# Analog_Interface.net
KiCad netlist of a schematic drawn in Altium Designer
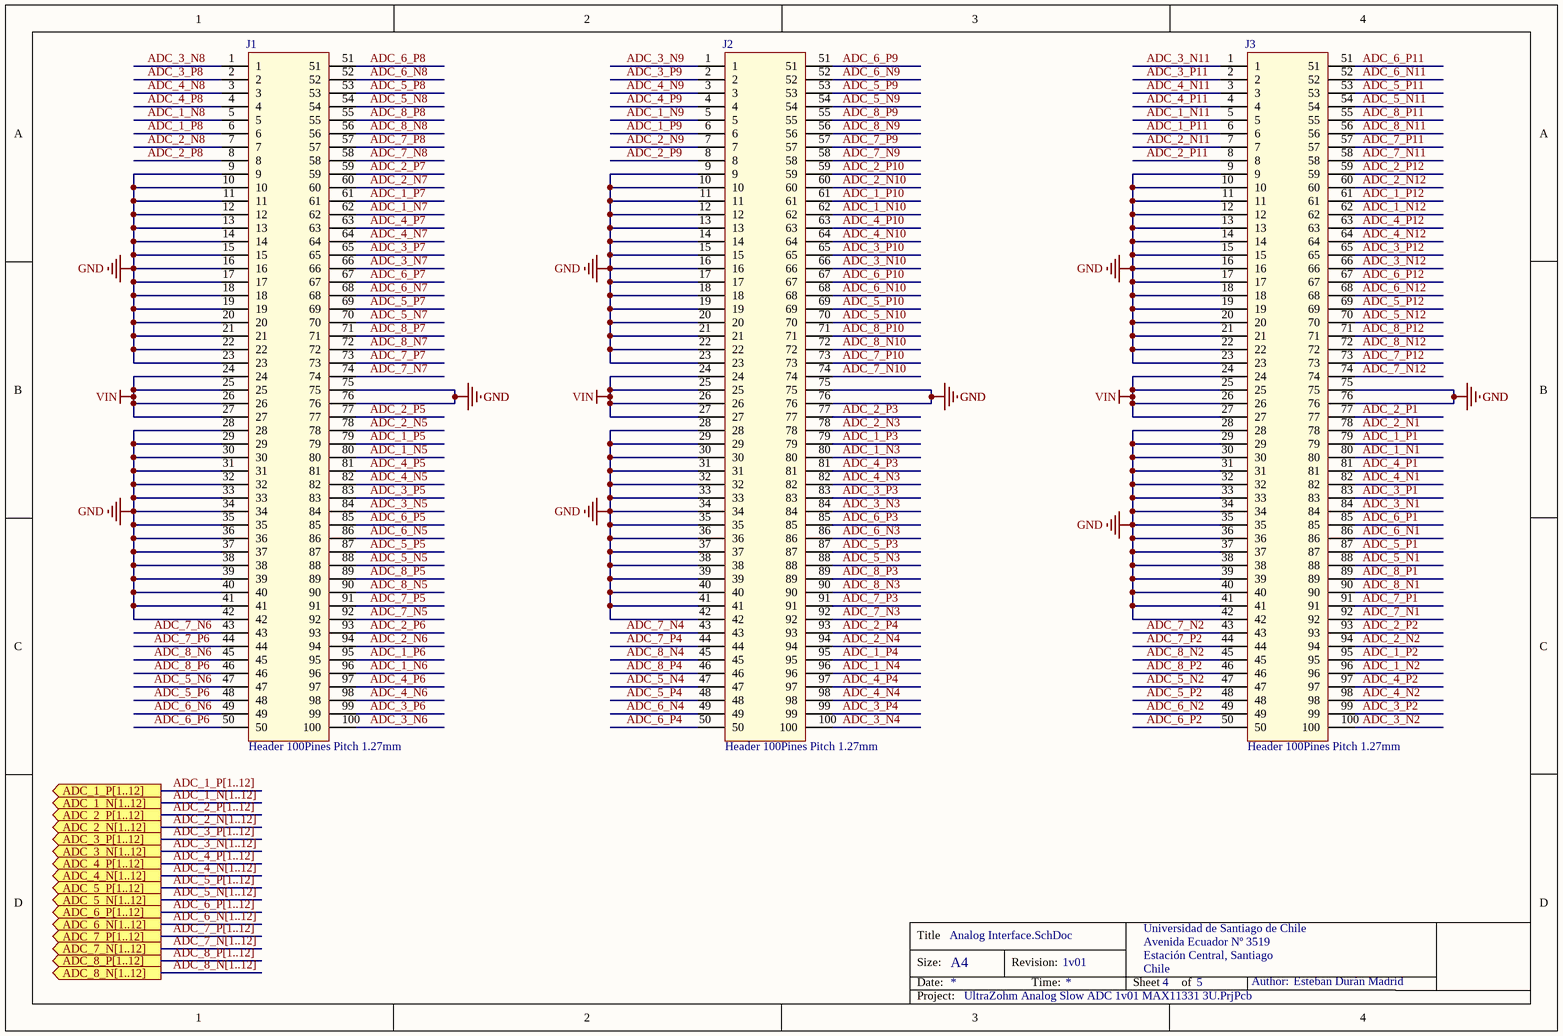
[diagram p0: Analog Interface.SchDoc]

(export (version "E")
  (design (tool "Eeschema 10.0.6"))
  (components
    (comp (ref "J1")
      (value "Header 100Pines Pitch 1.27mm")
      (footprint "Conector TE 100pines (2 filas) Pitch: 1.27mm")
      (description "6-104068-7")
      (libsource (lib "Componentes_SOC") (part "Header 100Pines Pitch 1.27mm"))
    )
    (comp (ref "J2")
      (value "Header 100Pines Pitch 1.27mm")
      (footprint "Conector TE 100pines (2 filas) Pitch: 1.27mm")
      (description "6-104068-7")
      (libsource (lib "Componentes_SOC") (part "Header 100Pines Pitch 1.27mm"))
    )
    (comp (ref "J3")
      (value "Header 100Pines Pitch 1.27mm")
      (footprint "Conector TE 100pines (2 filas) Pitch: 1.27mm")
      (description "6-104068-7")
      (libsource (lib "Componentes_SOC") (part "Header 100Pines Pitch 1.27mm"))
    )
  )
  (nets
    (net (code "1") (name "/ADC_1_N1") (class "Default")
      (node (ref "J3") (pin "80") (pinfunction "80_80") (pintype "passive"))
    )
    (net (code "2") (name "/ADC_1_N2") (class "Default")
      (node (ref "J3") (pin "96") (pinfunction "96_96") (pintype "passive"))
    )
    (net (code "3") (name "/ADC_1_N3") (class "Default")
      (node (ref "J2") (pin "80") (pinfunction "80_80") (pintype "passive"))
    )
    (net (code "4") (name "/ADC_1_N4") (class "Default")
      (node (ref "J2") (pin "96") (pinfunction "96_96") (pintype "passive"))
    )
    (net (code "5") (name "/ADC_1_N5") (class "Default")
      (node (ref "J1") (pin "80") (pinfunction "80_80") (pintype "passive"))
    )
    (net (code "6") (name "/ADC_1_N6") (class "Default")
      (node (ref "J1") (pin "96") (pinfunction "96_96") (pintype "passive"))
    )
    (net (code "7") (name "/ADC_1_N7") (class "Default")
      (node (ref "J1") (pin "62") (pinfunction "62_62") (pintype "passive"))
    )
    (net (code "8") (name "/ADC_1_N8") (class "Default")
      (node (ref "J1") (pin "5") (pinfunction "5_5") (pintype "passive"))
    )
    (net (code "9") (name "/ADC_1_N9") (class "Default")
      (node (ref "J2") (pin "5") (pinfunction "5_5") (pintype "passive"))
    )
    (net (code "10") (name "/ADC_1_N10") (class "Default")
      (node (ref "J2") (pin "62") (pinfunction "62_62") (pintype "passive"))
    )
    (net (code "11") (name "/ADC_1_N11") (class "Default")
      (node (ref "J3") (pin "5") (pinfunction "5_5") (pintype "passive"))
    )
    (net (code "12") (name "/ADC_1_N12") (class "Default")
      (node (ref "J3") (pin "62") (pinfunction "62_62") (pintype "passive"))
    )
    (net (code "14") (name "/ADC_1_P1") (class "Default")
      (node (ref "J3") (pin "79") (pinfunction "79_79") (pintype "passive"))
    )
    (net (code "15") (name "/ADC_1_P2") (class "Default")
      (node (ref "J3") (pin "95") (pinfunction "95_95") (pintype "passive"))
    )
    (net (code "16") (name "/ADC_1_P3") (class "Default")
      (node (ref "J2") (pin "79") (pinfunction "79_79") (pintype "passive"))
    )
    (net (code "17") (name "/ADC_1_P4") (class "Default")
      (node (ref "J2") (pin "95") (pinfunction "95_95") (pintype "passive"))
    )
    (net (code "18") (name "/ADC_1_P5") (class "Default")
      (node (ref "J1") (pin "79") (pinfunction "79_79") (pintype "passive"))
    )
    (net (code "19") (name "/ADC_1_P6") (class "Default")
      (node (ref "J1") (pin "95") (pinfunction "95_95") (pintype "passive"))
    )
    (net (code "20") (name "/ADC_1_P7") (class "Default")
      (node (ref "J1") (pin "61") (pinfunction "61_61") (pintype "passive"))
    )
    (net (code "21") (name "/ADC_1_P8") (class "Default")
      (node (ref "J1") (pin "6") (pinfunction "6_6") (pintype "passive"))
    )
    (net (code "22") (name "/ADC_1_P9") (class "Default")
      (node (ref "J2") (pin "6") (pinfunction "6_6") (pintype "passive"))
    )
    (net (code "23") (name "/ADC_1_P10") (class "Default")
      (node (ref "J2") (pin "61") (pinfunction "61_61") (pintype "passive"))
    )
    (net (code "24") (name "/ADC_1_P11") (class "Default")
      (node (ref "J3") (pin "6") (pinfunction "6_6") (pintype "passive"))
    )
    (net (code "25") (name "/ADC_1_P12") (class "Default")
      (node (ref "J3") (pin "61") (pinfunction "61_61") (pintype "passive"))
    )
    (net (code "27") (name "/ADC_2_N1") (class "Default")
      (node (ref "J3") (pin "78") (pinfunction "78_78") (pintype "passive"))
    )
    (net (code "28") (name "/ADC_2_N2") (class "Default")
      (node (ref "J3") (pin "94") (pinfunction "94_94") (pintype "passive"))
    )
    (net (code "29") (name "/ADC_2_N3") (class "Default")
      (node (ref "J2") (pin "78") (pinfunction "78_78") (pintype "passive"))
    )
    (net (code "30") (name "/ADC_2_N4") (class "Default")
      (node (ref "J2") (pin "94") (pinfunction "94_94") (pintype "passive"))
    )
    (net (code "31") (name "/ADC_2_N5") (class "Default")
      (node (ref "J1") (pin "78") (pinfunction "78_78") (pintype "passive"))
    )
    (net (code "32") (name "/ADC_2_N6") (class "Default")
      (node (ref "J1") (pin "94") (pinfunction "94_94") (pintype "passive"))
    )
    (net (code "33") (name "/ADC_2_N7") (class "Default")
      (node (ref "J1") (pin "60") (pinfunction "60_60") (pintype "passive"))
    )
    (net (code "34") (name "/ADC_2_N8") (class "Default")
      (node (ref "J1") (pin "7") (pinfunction "7_7") (pintype "passive"))
    )
    (net (code "35") (name "/ADC_2_N9") (class "Default")
      (node (ref "J2") (pin "7") (pinfunction "7_7") (pintype "passive"))
    )
    (net (code "36") (name "/ADC_2_N10") (class "Default")
      (node (ref "J2") (pin "60") (pinfunction "60_60") (pintype "passive"))
    )
    (net (code "37") (name "/ADC_2_N11") (class "Default")
      (node (ref "J3") (pin "7") (pinfunction "7_7") (pintype "passive"))
    )
    (net (code "38") (name "/ADC_2_N12") (class "Default")
      (node (ref "J3") (pin "60") (pinfunction "60_60") (pintype "passive"))
    )
    (net (code "40") (name "/ADC_2_P1") (class "Default")
      (node (ref "J3") (pin "77") (pinfunction "77_77") (pintype "passive"))
    )
    (net (code "41") (name "/ADC_2_P2") (class "Default")
      (node (ref "J3") (pin "93") (pinfunction "93_93") (pintype "passive"))
    )
    (net (code "42") (name "/ADC_2_P3") (class "Default")
      (node (ref "J2") (pin "77") (pinfunction "77_77") (pintype "passive"))
    )
    (net (code "43") (name "/ADC_2_P4") (class "Default")
      (node (ref "J2") (pin "93") (pinfunction "93_93") (pintype "passive"))
    )
    (net (code "44") (name "/ADC_2_P5") (class "Default")
      (node (ref "J1") (pin "77") (pinfunction "77_77") (pintype "passive"))
    )
    (net (code "45") (name "/ADC_2_P6") (class "Default")
      (node (ref "J1") (pin "93") (pinfunction "93_93") (pintype "passive"))
    )
    (net (code "46") (name "/ADC_2_P7") (class "Default")
      (node (ref "J1") (pin "59") (pinfunction "59_59") (pintype "passive"))
    )
    (net (code "47") (name "/ADC_2_P8") (class "Default")
      (node (ref "J1") (pin "8") (pinfunction "8_8") (pintype "passive"))
    )
    (net (code "48") (name "/ADC_2_P9") (class "Default")
      (node (ref "J2") (pin "8") (pinfunction "8_8") (pintype "passive"))
    )
    (net (code "49") (name "/ADC_2_P10") (class "Default")
      (node (ref "J2") (pin "59") (pinfunction "59_59") (pintype "passive"))
    )
    (net (code "50") (name "/ADC_2_P11") (class "Default")
      (node (ref "J3") (pin "8") (pinfunction "8_8") (pintype "passive"))
    )
    (net (code "51") (name "/ADC_2_P12") (class "Default")
      (node (ref "J3") (pin "59") (pinfunction "59_59") (pintype "passive"))
    )
    (net (code "53") (name "/ADC_3_N1") (class "Default")
      (node (ref "J3") (pin "84") (pinfunction "84_84") (pintype "passive"))
    )
    (net (code "54") (name "/ADC_3_N2") (class "Default")
      (node (ref "J3") (pin "100") (pinfunction "100_100") (pintype "passive"))
    )
    (net (code "55") (name "/ADC_3_N3") (class "Default")
      (node (ref "J2") (pin "84") (pinfunction "84_84") (pintype "passive"))
    )
    (net (code "56") (name "/ADC_3_N4") (class "Default")
      (node (ref "J2") (pin "100") (pinfunction "100_100") (pintype "passive"))
    )
    (net (code "57") (name "/ADC_3_N5") (class "Default")
      (node (ref "J1") (pin "84") (pinfunction "84_84") (pintype "passive"))
    )
    (net (code "58") (name "/ADC_3_N6") (class "Default")
      (node (ref "J1") (pin "100") (pinfunction "100_100") (pintype "passive"))
    )
    (net (code "59") (name "/ADC_3_N7") (class "Default")
      (node (ref "J1") (pin "66") (pinfunction "66_66") (pintype "passive"))
    )
    (net (code "60") (name "/ADC_3_N8") (class "Default")
      (node (ref "J1") (pin "1") (pinfunction "1_1") (pintype "passive"))
    )
    (net (code "61") (name "/ADC_3_N9") (class "Default")
      (node (ref "J2") (pin "1") (pinfunction "1_1") (pintype "passive"))
    )
    (net (code "62") (name "/ADC_3_N10") (class "Default")
      (node (ref "J2") (pin "66") (pinfunction "66_66") (pintype "passive"))
    )
    (net (code "63") (name "/ADC_3_N11") (class "Default")
      (node (ref "J3") (pin "1") (pinfunction "1_1") (pintype "passive"))
    )
    (net (code "64") (name "/ADC_3_N12") (class "Default")
      (node (ref "J3") (pin "66") (pinfunction "66_66") (pintype "passive"))
    )
    (net (code "66") (name "/ADC_3_P1") (class "Default")
      (node (ref "J3") (pin "83") (pinfunction "83_83") (pintype "passive"))
    )
    (net (code "67") (name "/ADC_3_P2") (class "Default")
      (node (ref "J3") (pin "99") (pinfunction "99_99") (pintype "passive"))
    )
    (net (code "68") (name "/ADC_3_P3") (class "Default")
      (node (ref "J2") (pin "83") (pinfunction "83_83") (pintype "passive"))
    )
    (net (code "69") (name "/ADC_3_P4") (class "Default")
      (node (ref "J2") (pin "99") (pinfunction "99_99") (pintype "passive"))
    )
    (net (code "70") (name "/ADC_3_P5") (class "Default")
      (node (ref "J1") (pin "83") (pinfunction "83_83") (pintype "passive"))
    )
    (net (code "71") (name "/ADC_3_P6") (class "Default")
      (node (ref "J1") (pin "99") (pinfunction "99_99") (pintype "passive"))
    )
    (net (code "72") (name "/ADC_3_P7") (class "Default")
      (node (ref "J1") (pin "65") (pinfunction "65_65") (pintype "passive"))
    )
    (net (code "73") (name "/ADC_3_P8") (class "Default")
      (node (ref "J1") (pin "2") (pinfunction "2_2") (pintype "passive"))
    )
    (net (code "74") (name "/ADC_3_P9") (class "Default")
      (node (ref "J2") (pin "2") (pinfunction "2_2") (pintype "passive"))
    )
    (net (code "75") (name "/ADC_3_P10") (class "Default")
      (node (ref "J2") (pin "65") (pinfunction "65_65") (pintype "passive"))
    )
    (net (code "76") (name "/ADC_3_P11") (class "Default")
      (node (ref "J3") (pin "2") (pinfunction "2_2") (pintype "passive"))
    )
    (net (code "77") (name "/ADC_3_P12") (class "Default")
      (node (ref "J3") (pin "65") (pinfunction "65_65") (pintype "passive"))
    )
    (net (code "79") (name "/ADC_4_N1") (class "Default")
      (node (ref "J3") (pin "82") (pinfunction "82_82") (pintype "passive"))
    )
    (net (code "80") (name "/ADC_4_N2") (class "Default")
      (node (ref "J3") (pin "98") (pinfunction "98_98") (pintype "passive"))
    )
    (net (code "81") (name "/ADC_4_N3") (class "Default")
      (node (ref "J2") (pin "82") (pinfunction "82_82") (pintype "passive"))
    )
    (net (code "82") (name "/ADC_4_N4") (class "Default")
      (node (ref "J2") (pin "98") (pinfunction "98_98") (pintype "passive"))
    )
    (net (code "83") (name "/ADC_4_N5") (class "Default")
      (node (ref "J1") (pin "82") (pinfunction "82_82") (pintype "passive"))
    )
    (net (code "84") (name "/ADC_4_N6") (class "Default")
      (node (ref "J1") (pin "98") (pinfunction "98_98") (pintype "passive"))
    )
    (net (code "85") (name "/ADC_4_N7") (class "Default")
      (node (ref "J1") (pin "64") (pinfunction "64_64") (pintype "passive"))
    )
    (net (code "86") (name "/ADC_4_N8") (class "Default")
      (node (ref "J1") (pin "3") (pinfunction "3_3") (pintype "passive"))
    )
    (net (code "87") (name "/ADC_4_N9") (class "Default")
      (node (ref "J2") (pin "3") (pinfunction "3_3") (pintype "passive"))
    )
    (net (code "88") (name "/ADC_4_N10") (class "Default")
      (node (ref "J2") (pin "64") (pinfunction "64_64") (pintype "passive"))
    )
    (net (code "89") (name "/ADC_4_N11") (class "Default")
      (node (ref "J3") (pin "3") (pinfunction "3_3") (pintype "passive"))
    )
    (net (code "90") (name "/ADC_4_N12") (class "Default")
      (node (ref "J3") (pin "64") (pinfunction "64_64") (pintype "passive"))
    )
    (net (code "92") (name "/ADC_4_P1") (class "Default")
      (node (ref "J3") (pin "81") (pinfunction "81_81") (pintype "passive"))
    )
    (net (code "93") (name "/ADC_4_P2") (class "Default")
      (node (ref "J3") (pin "97") (pinfunction "97_97") (pintype "passive"))
    )
    (net (code "94") (name "/ADC_4_P3") (class "Default")
      (node (ref "J2") (pin "81") (pinfunction "81_81") (pintype "passive"))
    )
    (net (code "95") (name "/ADC_4_P4") (class "Default")
      (node (ref "J2") (pin "97") (pinfunction "97_97") (pintype "passive"))
    )
    (net (code "96") (name "/ADC_4_P5") (class "Default")
      (node (ref "J1") (pin "81") (pinfunction "81_81") (pintype "passive"))
    )
    (net (code "97") (name "/ADC_4_P6") (class "Default")
      (node (ref "J1") (pin "97") (pinfunction "97_97") (pintype "passive"))
    )
    (net (code "98") (name "/ADC_4_P7") (class "Default")
      (node (ref "J1") (pin "63") (pinfunction "63_63") (pintype "passive"))
    )
    (net (code "99") (name "/ADC_4_P8") (class "Default")
      (node (ref "J1") (pin "4") (pinfunction "4_4") (pintype "passive"))
    )
    (net (code "100") (name "/ADC_4_P9") (class "Default")
      (node (ref "J2") (pin "4") (pinfunction "4_4") (pintype "passive"))
    )
    (net (code "101") (name "/ADC_4_P10") (class "Default")
      (node (ref "J2") (pin "63") (pinfunction "63_63") (pintype "passive"))
    )
    (net (code "102") (name "/ADC_4_P11") (class "Default")
      (node (ref "J3") (pin "4") (pinfunction "4_4") (pintype "passive"))
    )
    (net (code "103") (name "/ADC_4_P12") (class "Default")
      (node (ref "J3") (pin "63") (pinfunction "63_63") (pintype "passive"))
    )
    (net (code "105") (name "/ADC_5_N1") (class "Default")
      (node (ref "J3") (pin "88") (pinfunction "88_88") (pintype "passive"))
    )
    (net (code "106") (name "/ADC_5_N2") (class "Default")
      (node (ref "J3") (pin "47") (pinfunction "47_47") (pintype "passive"))
    )
    (net (code "107") (name "/ADC_5_N3") (class "Default")
      (node (ref "J2") (pin "88") (pinfunction "88_88") (pintype "passive"))
    )
    (net (code "108") (name "/ADC_5_N4") (class "Default")
      (node (ref "J2") (pin "47") (pinfunction "47_47") (pintype "passive"))
    )
    (net (code "109") (name "/ADC_5_N5") (class "Default")
      (node (ref "J1") (pin "88") (pinfunction "88_88") (pintype "passive"))
    )
    (net (code "110") (name "/ADC_5_N6") (class "Default")
      (node (ref "J1") (pin "47") (pinfunction "47_47") (pintype "passive"))
    )
    (net (code "111") (name "/ADC_5_N7") (class "Default")
      (node (ref "J1") (pin "70") (pinfunction "70_70") (pintype "passive"))
    )
    (net (code "112") (name "/ADC_5_N8") (class "Default")
      (node (ref "J1") (pin "54") (pinfunction "54_54") (pintype "passive"))
    )
    (net (code "113") (name "/ADC_5_N9") (class "Default")
      (node (ref "J2") (pin "54") (pinfunction "54_54") (pintype "passive"))
    )
    (net (code "114") (name "/ADC_5_N10") (class "Default")
      (node (ref "J2") (pin "70") (pinfunction "70_70") (pintype "passive"))
    )
    (net (code "115") (name "/ADC_5_N11") (class "Default")
      (node (ref "J3") (pin "54") (pinfunction "54_54") (pintype "passive"))
    )
    (net (code "116") (name "/ADC_5_N12") (class "Default")
      (node (ref "J3") (pin "70") (pinfunction "70_70") (pintype "passive"))
    )
    (net (code "118") (name "/ADC_5_P1") (class "Default")
      (node (ref "J3") (pin "87") (pinfunction "87_87") (pintype "passive"))
    )
    (net (code "119") (name "/ADC_5_P2") (class "Default")
      (node (ref "J3") (pin "48") (pinfunction "48_48") (pintype "passive"))
    )
    (net (code "120") (name "/ADC_5_P3") (class "Default")
      (node (ref "J2") (pin "87") (pinfunction "87_87") (pintype "passive"))
    )
    (net (code "121") (name "/ADC_5_P4") (class "Default")
      (node (ref "J2") (pin "48") (pinfunction "48_48") (pintype "passive"))
    )
    (net (code "122") (name "/ADC_5_P5") (class "Default")
      (node (ref "J1") (pin "87") (pinfunction "87_87") (pintype "passive"))
    )
    (net (code "123") (name "/ADC_5_P6") (class "Default")
      (node (ref "J1") (pin "48") (pinfunction "48_48") (pintype "passive"))
    )
    (net (code "124") (name "/ADC_5_P7") (class "Default")
      (node (ref "J1") (pin "69") (pinfunction "69_69") (pintype "passive"))
    )
    (net (code "125") (name "/ADC_5_P8") (class "Default")
      (node (ref "J1") (pin "53") (pinfunction "53_53") (pintype "passive"))
    )
    (net (code "126") (name "/ADC_5_P9") (class "Default")
      (node (ref "J2") (pin "53") (pinfunction "53_53") (pintype "passive"))
    )
    (net (code "127") (name "/ADC_5_P10") (class "Default")
      (node (ref "J2") (pin "69") (pinfunction "69_69") (pintype "passive"))
    )
    (net (code "128") (name "/ADC_5_P11") (class "Default")
      (node (ref "J3") (pin "53") (pinfunction "53_53") (pintype "passive"))
    )
    (net (code "129") (name "/ADC_5_P12") (class "Default")
      (node (ref "J3") (pin "69") (pinfunction "69_69") (pintype "passive"))
    )
    (net (code "131") (name "/ADC_6_N1") (class "Default")
      (node (ref "J3") (pin "86") (pinfunction "86_86") (pintype "passive"))
    )
    (net (code "132") (name "/ADC_6_N2") (class "Default")
      (node (ref "J3") (pin "49") (pinfunction "49_49") (pintype "passive"))
    )
    (net (code "133") (name "/ADC_6_N3") (class "Default")
      (node (ref "J2") (pin "86") (pinfunction "86_86") (pintype "passive"))
    )
    (net (code "134") (name "/ADC_6_N4") (class "Default")
      (node (ref "J2") (pin "49") (pinfunction "49_49") (pintype "passive"))
    )
    (net (code "135") (name "/ADC_6_N5") (class "Default")
      (node (ref "J1") (pin "86") (pinfunction "86_86") (pintype "passive"))
    )
    (net (code "136") (name "/ADC_6_N6") (class "Default")
      (node (ref "J1") (pin "49") (pinfunction "49_49") (pintype "passive"))
    )
    (net (code "137") (name "/ADC_6_N7") (class "Default")
      (node (ref "J1") (pin "68") (pinfunction "68_68") (pintype "passive"))
    )
    (net (code "138") (name "/ADC_6_N8") (class "Default")
      (node (ref "J1") (pin "52") (pinfunction "52_52") (pintype "passive"))
    )
    (net (code "139") (name "/ADC_6_N9") (class "Default")
      (node (ref "J2") (pin "52") (pinfunction "52_52") (pintype "passive"))
    )
    (net (code "140") (name "/ADC_6_N10") (class "Default")
      (node (ref "J2") (pin "68") (pinfunction "68_68") (pintype "passive"))
    )
    (net (code "141") (name "/ADC_6_N11") (class "Default")
      (node (ref "J3") (pin "52") (pinfunction "52_52") (pintype "passive"))
    )
    (net (code "142") (name "/ADC_6_N12") (class "Default")
      (node (ref "J3") (pin "68") (pinfunction "68_68") (pintype "passive"))
    )
    (net (code "144") (name "/ADC_6_P1") (class "Default")
      (node (ref "J3") (pin "85") (pinfunction "85_85") (pintype "passive"))
    )
    (net (code "145") (name "/ADC_6_P2") (class "Default")
      (node (ref "J3") (pin "50") (pinfunction "50_50") (pintype "passive"))
    )
    (net (code "146") (name "/ADC_6_P3") (class "Default")
      (node (ref "J2") (pin "85") (pinfunction "85_85") (pintype "passive"))
    )
    (net (code "147") (name "/ADC_6_P4") (class "Default")
      (node (ref "J2") (pin "50") (pinfunction "50_50") (pintype "passive"))
    )
    (net (code "148") (name "/ADC_6_P5") (class "Default")
      (node (ref "J1") (pin "85") (pinfunction "85_85") (pintype "passive"))
    )
    (net (code "149") (name "/ADC_6_P6") (class "Default")
      (node (ref "J1") (pin "50") (pinfunction "50_50") (pintype "passive"))
    )
    (net (code "150") (name "/ADC_6_P7") (class "Default")
      (node (ref "J1") (pin "67") (pinfunction "67_67") (pintype "passive"))
    )
    (net (code "151") (name "/ADC_6_P8") (class "Default")
      (node (ref "J1") (pin "51") (pinfunction "51_51") (pintype "passive"))
    )
    (net (code "152") (name "/ADC_6_P9") (class "Default")
      (node (ref "J2") (pin "51") (pinfunction "51_51") (pintype "passive"))
    )
    (net (code "153") (name "/ADC_6_P10") (class "Default")
      (node (ref "J2") (pin "67") (pinfunction "67_67") (pintype "passive"))
    )
    (net (code "154") (name "/ADC_6_P11") (class "Default")
      (node (ref "J3") (pin "51") (pinfunction "51_51") (pintype "passive"))
    )
    (net (code "155") (name "/ADC_6_P12") (class "Default")
      (node (ref "J3") (pin "67") (pinfunction "67_67") (pintype "passive"))
    )
    (net (code "157") (name "/ADC_7_N1") (class "Default")
      (node (ref "J3") (pin "92") (pinfunction "92_92") (pintype "passive"))
    )
    (net (code "158") (name "/ADC_7_N2") (class "Default")
      (node (ref "J3") (pin "43") (pinfunction "43_43") (pintype "passive"))
    )
    (net (code "159") (name "/ADC_7_N3") (class "Default")
      (node (ref "J2") (pin "92") (pinfunction "92_92") (pintype "passive"))
    )
    (net (code "160") (name "/ADC_7_N4") (class "Default")
      (node (ref "J2") (pin "43") (pinfunction "43_43") (pintype "passive"))
    )
    (net (code "161") (name "/ADC_7_N5") (class "Default")
      (node (ref "J1") (pin "92") (pinfunction "92_92") (pintype "passive"))
    )
    (net (code "162") (name "/ADC_7_N6") (class "Default")
      (node (ref "J1") (pin "43") (pinfunction "43_43") (pintype "passive"))
    )
    (net (code "163") (name "/ADC_7_N7") (class "Default")
      (node (ref "J1") (pin "74") (pinfunction "74_74") (pintype "passive"))
    )
    (net (code "164") (name "/ADC_7_N8") (class "Default")
      (node (ref "J1") (pin "58") (pinfunction "58_58") (pintype "passive"))
    )
    (net (code "165") (name "/ADC_7_N9") (class "Default")
      (node (ref "J2") (pin "58") (pinfunction "58_58") (pintype "passive"))
    )
    (net (code "166") (name "/ADC_7_N10") (class "Default")
      (node (ref "J2") (pin "74") (pinfunction "74_74") (pintype "passive"))
    )
    (net (code "167") (name "/ADC_7_N11") (class "Default")
      (node (ref "J3") (pin "58") (pinfunction "58_58") (pintype "passive"))
    )
    (net (code "168") (name "/ADC_7_N12") (class "Default")
      (node (ref "J3") (pin "74") (pinfunction "74_74") (pintype "passive"))
    )
    (net (code "170") (name "/ADC_7_P1") (class "Default")
      (node (ref "J3") (pin "91") (pinfunction "91_91") (pintype "passive"))
    )
    (net (code "171") (name "/ADC_7_P2") (class "Default")
      (node (ref "J3") (pin "44") (pinfunction "44_44") (pintype "passive"))
    )
    (net (code "172") (name "/ADC_7_P3") (class "Default")
      (node (ref "J2") (pin "91") (pinfunction "91_91") (pintype "passive"))
    )
    (net (code "173") (name "/ADC_7_P4") (class "Default")
      (node (ref "J2") (pin "44") (pinfunction "44_44") (pintype "passive"))
    )
    (net (code "174") (name "/ADC_7_P5") (class "Default")
      (node (ref "J1") (pin "91") (pinfunction "91_91") (pintype "passive"))
    )
    (net (code "175") (name "/ADC_7_P6") (class "Default")
      (node (ref "J1") (pin "44") (pinfunction "44_44") (pintype "passive"))
    )
    (net (code "176") (name "/ADC_7_P7") (class "Default")
      (node (ref "J1") (pin "73") (pinfunction "73_73") (pintype "passive"))
    )
    (net (code "177") (name "/ADC_7_P8") (class "Default")
      (node (ref "J1") (pin "57") (pinfunction "57_57") (pintype "passive"))
    )
    (net (code "178") (name "/ADC_7_P9") (class "Default")
      (node (ref "J2") (pin "57") (pinfunction "57_57") (pintype "passive"))
    )
    (net (code "179") (name "/ADC_7_P10") (class "Default")
      (node (ref "J2") (pin "73") (pinfunction "73_73") (pintype "passive"))
    )
    (net (code "180") (name "/ADC_7_P11") (class "Default")
      (node (ref "J3") (pin "57") (pinfunction "57_57") (pintype "passive"))
    )
    (net (code "181") (name "/ADC_7_P12") (class "Default")
      (node (ref "J3") (pin "73") (pinfunction "73_73") (pintype "passive"))
    )
    (net (code "183") (name "/ADC_8_N1") (class "Default")
      (node (ref "J3") (pin "90") (pinfunction "90_90") (pintype "passive"))
    )
    (net (code "184") (name "/ADC_8_N2") (class "Default")
      (node (ref "J3") (pin "45") (pinfunction "45_45") (pintype "passive"))
    )
    (net (code "185") (name "/ADC_8_N3") (class "Default")
      (node (ref "J2") (pin "90") (pinfunction "90_90") (pintype "passive"))
    )
    (net (code "186") (name "/ADC_8_N4") (class "Default")
      (node (ref "J2") (pin "45") (pinfunction "45_45") (pintype "passive"))
    )
    (net (code "187") (name "/ADC_8_N5") (class "Default")
      (node (ref "J1") (pin "90") (pinfunction "90_90") (pintype "passive"))
    )
    (net (code "188") (name "/ADC_8_N6") (class "Default")
      (node (ref "J1") (pin "45") (pinfunction "45_45") (pintype "passive"))
    )
    (net (code "189") (name "/ADC_8_N7") (class "Default")
      (node (ref "J1") (pin "72") (pinfunction "72_72") (pintype "passive"))
    )
    (net (code "190") (name "/ADC_8_N8") (class "Default")
      (node (ref "J1") (pin "56") (pinfunction "56_56") (pintype "passive"))
    )
    (net (code "191") (name "/ADC_8_N9") (class "Default")
      (node (ref "J2") (pin "56") (pinfunction "56_56") (pintype "passive"))
    )
    (net (code "192") (name "/ADC_8_N10") (class "Default")
      (node (ref "J2") (pin "72") (pinfunction "72_72") (pintype "passive"))
    )
    (net (code "193") (name "/ADC_8_N11") (class "Default")
      (node (ref "J3") (pin "56") (pinfunction "56_56") (pintype "passive"))
    )
    (net (code "194") (name "/ADC_8_N12") (class "Default")
      (node (ref "J3") (pin "72") (pinfunction "72_72") (pintype "passive"))
    )
    (net (code "196") (name "/ADC_8_P1") (class "Default")
      (node (ref "J3") (pin "89") (pinfunction "89_89") (pintype "passive"))
    )
    (net (code "197") (name "/ADC_8_P2") (class "Default")
      (node (ref "J3") (pin "46") (pinfunction "46_46") (pintype "passive"))
    )
    (net (code "198") (name "/ADC_8_P3") (class "Default")
      (node (ref "J2") (pin "89") (pinfunction "89_89") (pintype "passive"))
    )
    (net (code "199") (name "/ADC_8_P4") (class "Default")
      (node (ref "J2") (pin "46") (pinfunction "46_46") (pintype "passive"))
    )
    (net (code "200") (name "/ADC_8_P5") (class "Default")
      (node (ref "J1") (pin "89") (pinfunction "89_89") (pintype "passive"))
    )
    (net (code "201") (name "/ADC_8_P6") (class "Default")
      (node (ref "J1") (pin "46") (pinfunction "46_46") (pintype "passive"))
    )
    (net (code "202") (name "/ADC_8_P7") (class "Default")
      (node (ref "J1") (pin "71") (pinfunction "71_71") (pintype "passive"))
    )
    (net (code "203") (name "/ADC_8_P8") (class "Default")
      (node (ref "J1") (pin "55") (pinfunction "55_55") (pintype "passive"))
    )
    (net (code "204") (name "/ADC_8_P9") (class "Default")
      (node (ref "J2") (pin "55") (pinfunction "55_55") (pintype "passive"))
    )
    (net (code "205") (name "/ADC_8_P10") (class "Default")
      (node (ref "J2") (pin "71") (pinfunction "71_71") (pintype "passive"))
    )
    (net (code "206") (name "/ADC_8_P11") (class "Default")
      (node (ref "J3") (pin "55") (pinfunction "55_55") (pintype "passive"))
    )
    (net (code "207") (name "/ADC_8_P12") (class "Default")
      (node (ref "J3") (pin "71") (pinfunction "71_71") (pintype "passive"))
    )
    (net (code "209") (name "GND") (class "Default")
      (node (ref "J1") (pin "10") (pinfunction "10_10") (pintype "passive"))
      (node (ref "J1") (pin "11") (pinfunction "11_11") (pintype "passive"))
      (node (ref "J1") (pin "12") (pinfunction "12_12") (pintype "passive"))
      (node (ref "J1") (pin "13") (pinfunction "13_13") (pintype "passive"))
      (node (ref "J1") (pin "14") (pinfunction "14_14") (pintype "passive"))
      (node (ref "J1") (pin "15") (pinfunction "15_15") (pintype "passive"))
      (node (ref "J1") (pin "16") (pinfunction "16_16") (pintype "passive"))
      (node (ref "J1") (pin "17") (pinfunction "17_17") (pintype "passive"))
      (node (ref "J1") (pin "18") (pinfunction "18_18") (pintype "passive"))
      (node (ref "J1") (pin "19") (pinfunction "19_19") (pintype "passive"))
      (node (ref "J1") (pin "20") (pinfunction "20_20") (pintype "passive"))
      (node (ref "J1") (pin "21") (pinfunction "21_21") (pintype "passive"))
      (node (ref "J1") (pin "22") (pinfunction "22_22") (pintype "passive"))
      (node (ref "J1") (pin "23") (pinfunction "23_23") (pintype "passive"))
      (node (ref "J1") (pin "28") (pinfunction "28_28") (pintype "passive"))
      (node (ref "J1") (pin "29") (pinfunction "29_29") (pintype "passive"))
      (node (ref "J1") (pin "30") (pinfunction "30_30") (pintype "passive"))
      (node (ref "J1") (pin "31") (pinfunction "31_31") (pintype "passive"))
      (node (ref "J1") (pin "32") (pinfunction "32_32") (pintype "passive"))
      (node (ref "J1") (pin "33") (pinfunction "33_33") (pintype "passive"))
      (node (ref "J1") (pin "34") (pinfunction "34_34") (pintype "passive"))
      (node (ref "J1") (pin "35") (pinfunction "35_35") (pintype "passive"))
      (node (ref "J1") (pin "36") (pinfunction "36_36") (pintype "passive"))
      (node (ref "J1") (pin "37") (pinfunction "37_37") (pintype "passive"))
      (node (ref "J1") (pin "38") (pinfunction "38_38") (pintype "passive"))
      (node (ref "J1") (pin "39") (pinfunction "39_39") (pintype "passive"))
      (node (ref "J1") (pin "40") (pinfunction "40_40") (pintype "passive"))
      (node (ref "J1") (pin "41") (pinfunction "41_41") (pintype "passive"))
      (node (ref "J1") (pin "42") (pinfunction "42_42") (pintype "passive"))
      (node (ref "J1") (pin "75") (pinfunction "75_75") (pintype "passive"))
      (node (ref "J1") (pin "76") (pinfunction "76_76") (pintype "passive"))
      (node (ref "J1") (pin "9") (pinfunction "9_9") (pintype "passive"))
      (node (ref "J2") (pin "10") (pinfunction "10_10") (pintype "passive"))
      (node (ref "J2") (pin "11") (pinfunction "11_11") (pintype "passive"))
      (node (ref "J2") (pin "12") (pinfunction "12_12") (pintype "passive"))
      (node (ref "J2") (pin "13") (pinfunction "13_13") (pintype "passive"))
      (node (ref "J2") (pin "14") (pinfunction "14_14") (pintype "passive"))
      (node (ref "J2") (pin "15") (pinfunction "15_15") (pintype "passive"))
      (node (ref "J2") (pin "16") (pinfunction "16_16") (pintype "passive"))
      (node (ref "J2") (pin "17") (pinfunction "17_17") (pintype "passive"))
      (node (ref "J2") (pin "18") (pinfunction "18_18") (pintype "passive"))
      (node (ref "J2") (pin "19") (pinfunction "19_19") (pintype "passive"))
      (node (ref "J2") (pin "20") (pinfunction "20_20") (pintype "passive"))
      (node (ref "J2") (pin "21") (pinfunction "21_21") (pintype "passive"))
      (node (ref "J2") (pin "22") (pinfunction "22_22") (pintype "passive"))
      (node (ref "J2") (pin "23") (pinfunction "23_23") (pintype "passive"))
      (node (ref "J2") (pin "28") (pinfunction "28_28") (pintype "passive"))
      (node (ref "J2") (pin "29") (pinfunction "29_29") (pintype "passive"))
      (node (ref "J2") (pin "30") (pinfunction "30_30") (pintype "passive"))
      (node (ref "J2") (pin "31") (pinfunction "31_31") (pintype "passive"))
      (node (ref "J2") (pin "32") (pinfunction "32_32") (pintype "passive"))
      (node (ref "J2") (pin "33") (pinfunction "33_33") (pintype "passive"))
      (node (ref "J2") (pin "34") (pinfunction "34_34") (pintype "passive"))
      (node (ref "J2") (pin "35") (pinfunction "35_35") (pintype "passive"))
      (node (ref "J2") (pin "36") (pinfunction "36_36") (pintype "passive"))
      (node (ref "J2") (pin "37") (pinfunction "37_37") (pintype "passive"))
      (node (ref "J2") (pin "38") (pinfunction "38_38") (pintype "passive"))
      (node (ref "J2") (pin "39") (pinfunction "39_39") (pintype "passive"))
      (node (ref "J2") (pin "40") (pinfunction "40_40") (pintype "passive"))
      (node (ref "J2") (pin "41") (pinfunction "41_41") (pintype "passive"))
      (node (ref "J2") (pin "42") (pinfunction "42_42") (pintype "passive"))
      (node (ref "J2") (pin "75") (pinfunction "75_75") (pintype "passive"))
      (node (ref "J2") (pin "76") (pinfunction "76_76") (pintype "passive"))
      (node (ref "J2") (pin "9") (pinfunction "9_9") (pintype "passive"))
      (node (ref "J3") (pin "10") (pinfunction "10_10") (pintype "passive"))
      (node (ref "J3") (pin "11") (pinfunction "11_11") (pintype "passive"))
      (node (ref "J3") (pin "12") (pinfunction "12_12") (pintype "passive"))
      (node (ref "J3") (pin "13") (pinfunction "13_13") (pintype "passive"))
      (node (ref "J3") (pin "14") (pinfunction "14_14") (pintype "passive"))
      (node (ref "J3") (pin "15") (pinfunction "15_15") (pintype "passive"))
      (node (ref "J3") (pin "16") (pinfunction "16_16") (pintype "passive"))
      (node (ref "J3") (pin "17") (pinfunction "17_17") (pintype "passive"))
      (node (ref "J3") (pin "18") (pinfunction "18_18") (pintype "passive"))
      (node (ref "J3") (pin "19") (pinfunction "19_19") (pintype "passive"))
      (node (ref "J3") (pin "20") (pinfunction "20_20") (pintype "passive"))
      (node (ref "J3") (pin "21") (pinfunction "21_21") (pintype "passive"))
      (node (ref "J3") (pin "22") (pinfunction "22_22") (pintype "passive"))
      (node (ref "J3") (pin "23") (pinfunction "23_23") (pintype "passive"))
      (node (ref "J3") (pin "28") (pinfunction "28_28") (pintype "passive"))
      (node (ref "J3") (pin "29") (pinfunction "29_29") (pintype "passive"))
      (node (ref "J3") (pin "30") (pinfunction "30_30") (pintype "passive"))
      (node (ref "J3") (pin "31") (pinfunction "31_31") (pintype "passive"))
      (node (ref "J3") (pin "32") (pinfunction "32_32") (pintype "passive"))
      (node (ref "J3") (pin "33") (pinfunction "33_33") (pintype "passive"))
      (node (ref "J3") (pin "34") (pinfunction "34_34") (pintype "passive"))
      (node (ref "J3") (pin "35") (pinfunction "35_35") (pintype "passive"))
      (node (ref "J3") (pin "36") (pinfunction "36_36") (pintype "passive"))
      (node (ref "J3") (pin "37") (pinfunction "37_37") (pintype "passive"))
      (node (ref "J3") (pin "38") (pinfunction "38_38") (pintype "passive"))
      (node (ref "J3") (pin "39") (pinfunction "39_39") (pintype "passive"))
      (node (ref "J3") (pin "40") (pinfunction "40_40") (pintype "passive"))
      (node (ref "J3") (pin "41") (pinfunction "41_41") (pintype "passive"))
      (node (ref "J3") (pin "42") (pinfunction "42_42") (pintype "passive"))
      (node (ref "J3") (pin "75") (pinfunction "75_75") (pintype "passive"))
      (node (ref "J3") (pin "76") (pinfunction "76_76") (pintype "passive"))
      (node (ref "J3") (pin "9") (pinfunction "9_9") (pintype "passive"))
    )
    (net (code "210") (name "VIN") (class "Default")
      (node (ref "J1") (pin "24") (pinfunction "24_24") (pintype "passive"))
      (node (ref "J1") (pin "25") (pinfunction "25_25") (pintype "passive"))
      (node (ref "J1") (pin "26") (pinfunction "26_26") (pintype "passive"))
      (node (ref "J1") (pin "27") (pinfunction "27_27") (pintype "passive"))
      (node (ref "J2") (pin "24") (pinfunction "24_24") (pintype "passive"))
      (node (ref "J2") (pin "25") (pinfunction "25_25") (pintype "passive"))
      (node (ref "J2") (pin "26") (pinfunction "26_26") (pintype "passive"))
      (node (ref "J2") (pin "27") (pinfunction "27_27") (pintype "passive"))
      (node (ref "J3") (pin "24") (pinfunction "24_24") (pintype "passive"))
      (node (ref "J3") (pin "25") (pinfunction "25_25") (pintype "passive"))
      (node (ref "J3") (pin "26") (pinfunction "26_26") (pintype "passive"))
      (node (ref "J3") (pin "27") (pinfunction "27_27") (pintype "passive"))
    )
  )
)
